# 3V3_DIST_ZYNQ.net
KiCad netlist of a schematic drawn in Altium Designer
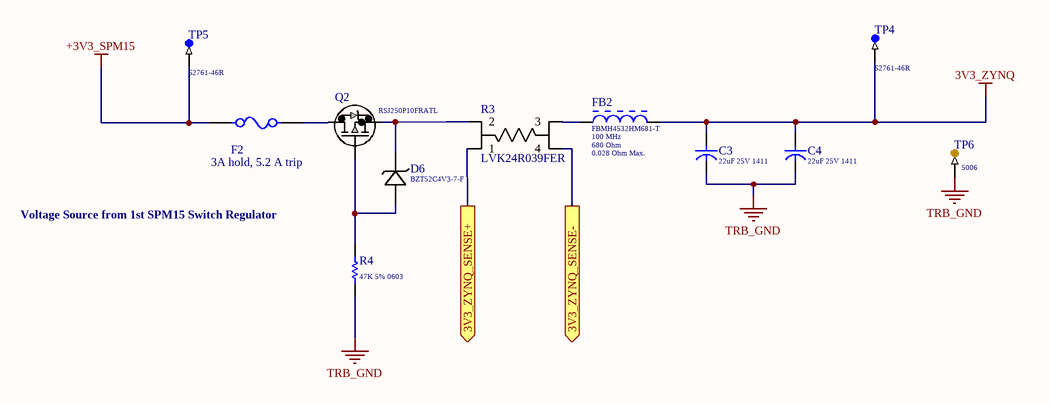
[diagram p0: 3V3_DIST_ZYNQ.SchDoc]

(export (version "E")
  (design (tool "Eeschema 10.0.6"))
  (components
    (comp (ref "C3")
      (value "Cap_Kemet_T521B226M025ATE100_22uF")
      (footprint "Cap_Kemet_T521B226M025ATE100_22uF")
      (description "Tantalum Capacitors - Polymer SMD 25V 22uF 1311 20% ESR=100mOhms")
      (fields (field (name "CAPACITANCE") "22uF 25V 1411"))
      (libsource (lib "Cap_Kemet_T521B226M025ATE100_22uF") (part "Cap_Kemet_T521B226M025ATE100_22uF"))
    )
    (comp (ref "C4")
      (value "Cap_Kemet_T521B226M025ATE100_22uF")
      (footprint "Cap_Kemet_T521B226M025ATE100_22uF")
      (description "Tantalum Capacitors - Polymer SMD 25V 22uF 1311 20% ESR=100mOhms")
      (fields (field (name "CAPACITANCE") "22uF 25V 1411"))
      (libsource (lib "Cap_Kemet_T521B226M025ATE100_22uF") (part "Cap_Kemet_T521B226M025ATE100_22uF"))
    )
    (comp (ref "D6")
      (value "BZT52C4V3-7-F")
      (footprint "SOD123")
      (description "Zener Diodes 500mW 4.3V Zener AEC-Q101 Qualified")
      (fields (field (name "SERIES") "BZT52C4V3-7-F"))
      (libsource (lib "4v3_zener_BZT52C4V3-7-F") (part "BZT52C4V3-7-F"))
    )
    (comp (ref "F2")
      (value "3A hold, 5.2 A trip")
      (footprint "Bel_0ZCF_MFG")
      (description "Resettable Fuses - PPTC 3A 24V PPTC 2920 SMD")
      (libsource (lib "Fuse_Bel_0ZCF0300BF2C_3A_hold") (part "0ZCF0300BF2C"))
    )
    (comp (ref "FB2")
      (value "FBMH4532HM681-T")
      (footprint "TAYO-FBMH4532-2_V")
      (fields
        (field (name "PARTNUMBER") "FBMH4532HM681-T")
        (field (name "MANUFACTURER") "Taiyo Yuden")
        (field (name "MEASURING FREQUENCY") "100 MHz")
        (field (name "NOMINAL IMPEDANCE") "680 Ohm")
        (field (name "DC RESISTANCE") "0.028 Ohm Max.")
      )
      (libsource (lib "Taiyo_Yuden_FBMH4532HM681") (part "FBMH4532HM681-T"))
    )
    (comp (ref "Q2")
      (value "Mos_ROHM_RSJ250P10FRATL_25A")
      (footprint "Mos_ROHM_RSJ250P10FRATL_25A")
      (description "MOSFET Pch -100V Vds -25A 0.05Rds(on) 60Qg")
      (fields (field (name "SERIES") "RSJ250P10FRATL"))
      (libsource (lib "Mos_ROHM_RSJ250P10FRATL_25A") (part "Mos_ROHM_RSJ250P10FRATL_25A"))
    )
    (comp (ref "R3")
      (value "LVK24R039FER")
      (footprint "OH_LVK24_OHM")
      (description "RES 0.039 OHM 1% 1W 2412")
      (fields (field (name "COPYRIGHT") "Copyright (C) 2018 Accelerated Designs. All rights reserved"))
      (libsource (lib "Shunt_Res_Ohmite_LVK24R039FER") (part "LVK24R039FER"))
    )
    (comp (ref "R4")
      (value "47K 5% 0603")
      (footprint "RESC0603(1608)_L")
      (description "47K 0.1W 5% 0603 (1608 Metric)  SMD")
      (fields (field (name "TOLERANCE") "5 %") (field (name "POWER") "0.1 W"))
      (libsource (lib "Altium Content Vault") (part "RES"))
    )
    (comp (ref "TP4")
      (value "TP_Harwin_S2761_46R")
      (footprint "TP_Harwin_S2761_46R")
      (description "Circuit Board Hardware - PCB SMT Mini Test Terminal, Reel")
      (fields (field (name "SERIES") "S2761-46R"))
      (libsource (lib "TP_Harwin_S2761_46R") (part "TP_Harwin_S2761_46R"))
    )
    (comp (ref "TP5")
      (value "TP_Harwin_S2761_46R")
      (footprint "TP_Harwin_S2761_46R")
      (description "Circuit Board Hardware - PCB SMT Mini Test Terminal, Reel")
      (fields (field (name "SERIES") "S2761-46R"))
      (libsource (lib "TP_Harwin_S2761_46R") (part "TP_Harwin_S2761_46R"))
    )
    (comp (ref "TP6")
      (value "TP_Keystone_Electronics_5006")
      (footprint "TP_Keystone_Electronics_5006")
      (description "Circuit Board Hardware - PCB TEST POINT BLK .063")
      (fields (field (name "SERIES") "5006"))
      (libsource (lib "TP_Keystone_Electronics_5006") (part "TP_Keystone_Electronics_5006"))
    )
  )
  (nets
    (net (code "1") (name "+3V3_SPM15") (class "Default")
      (node (ref "F2") (pin "1") (pinfunction "1_1") (pintype "passive"))
      (node (ref "TP5") (pin "1") (pinfunction "1_1") (pintype "input"))
    )
    (net (code "2") (name "/3V3_ZYNQ_SENSE+") (class "Default")
      (node (ref "R3") (pin "1") (pinfunction "1_1") (pintype "passive"))
    )
    (net (code "3") (name "/3V3_ZYNQ_SENSE-") (class "Default")
      (node (ref "R3") (pin "4") (pinfunction "4_4") (pintype "passive"))
    )
    (net (code "4") (name "3V3_ZYNQ") (class "Default")
      (node (ref "C3") (pin "1") (pinfunction "1_1") (pintype "passive"))
      (node (ref "C4") (pin "1") (pinfunction "1_1") (pintype "passive"))
      (node (ref "FB2") (pin "2") (pinfunction "2_2") (pintype "passive"))
      (node (ref "TP4") (pin "1") (pinfunction "1_1") (pintype "input"))
    )
    (net (code "5") (name "Net-(FB2-Pad1)") (class "Default")
      (node (ref "FB2") (pin "1") (pinfunction "1_1") (pintype "passive"))
      (node (ref "R3") (pin "3") (pinfunction "3_3") (pintype "passive"))
    )
    (net (code "6") (name "Net-(Q2-D)") (class "Default")
      (node (ref "F2") (pin "2") (pinfunction "2_2") (pintype "passive"))
      (node (ref "Q2") (pin "2") (pinfunction "D_2") (pintype "passive"))
    )
    (net (code "7") (name "Net-(Q2-G)") (class "Default")
      (node (ref "D6") (pin "2") (pinfunction "2_2") (pintype "passive"))
      (node (ref "Q2") (pin "1") (pinfunction "G_1") (pintype "passive"))
      (node (ref "R4") (pin "2") (pinfunction "2_2") (pintype "passive"))
    )
    (net (code "8") (name "Net-(Q2-S)") (class "Default")
      (node (ref "D6") (pin "1") (pinfunction "1_1") (pintype "passive"))
      (node (ref "Q2") (pin "3") (pinfunction "S_3") (pintype "passive"))
      (node (ref "R3") (pin "2") (pinfunction "2_2") (pintype "passive"))
    )
    (net (code "9") (name "TRB_GND") (class "Default")
      (node (ref "C3") (pin "2") (pinfunction "2_2") (pintype "passive"))
      (node (ref "C4") (pin "2") (pinfunction "2_2") (pintype "passive"))
      (node (ref "R4") (pin "1") (pinfunction "1_1") (pintype "passive"))
      (node (ref "TP6") (pin "1") (pinfunction "1_1") (pintype "input"))
    )
  )
)
